# 09_-_COMMUNICATION.net
KiCad netlist of a schematic drawn in Altium Designer
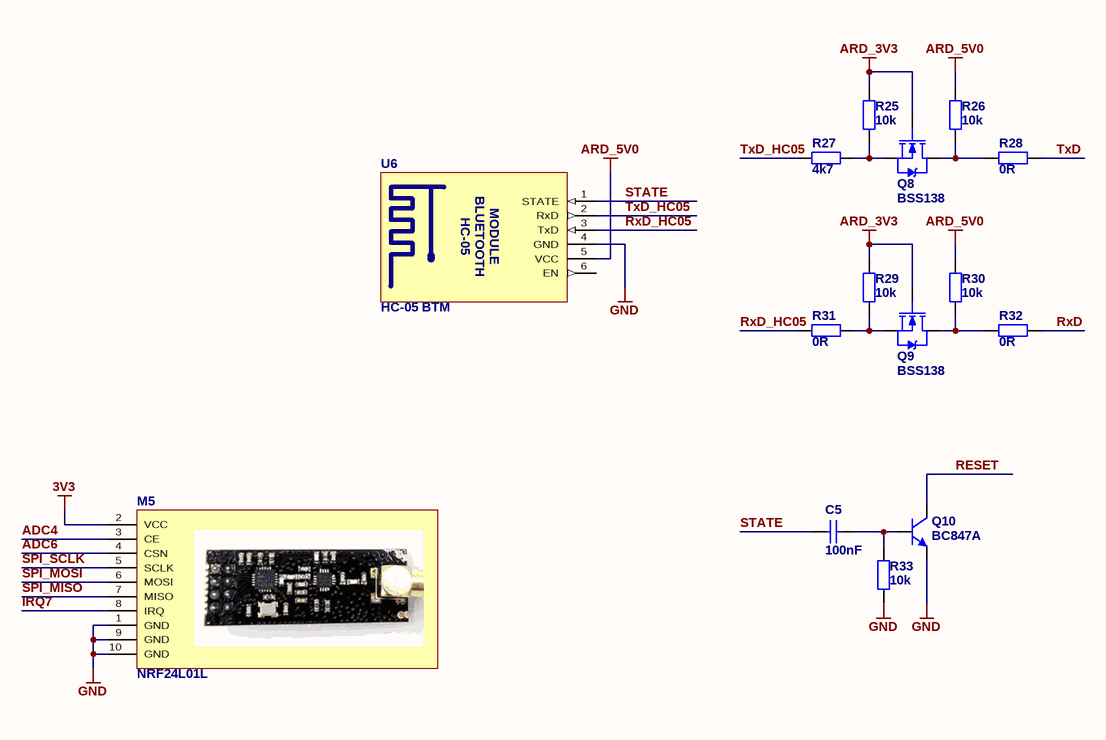
[diagram p0: [09] - COMMUNICATION.SchDoc]

(export (version "E")
  (design (tool "Eeschema 10.0.6"))
  (components
    (comp (ref "C5")
      (value "100nF")
      (footprint "C0805")
      (description "Capacitor")
      (libsource (lib "capacitors") (part "Cap"))
    )
    (comp (ref "M5")
      (value "NRF24L01L")
      (footprint "NRF24L01L")
      (description "Long Range Wireless Module R2 (1.1KM, PA+SMA)")
      (libsource (lib "wireless_modules") (part "NRF24L01L"))
    )
    (comp (ref "Q8")
      (value "BSS138")
      (footprint "SOT-23")
      (description "N-Channel Enhancement Mode Vertical DMOS FET")
      (fields (field (name "PUBLISHER") "Altium Limited"))
      (libsource (lib "transistors_mos") (part "BSS138"))
    )
    (comp (ref "Q9")
      (value "BSS138")
      (footprint "SOT-23")
      (description "N-Channel Enhancement Mode Vertical DMOS FET")
      (fields (field (name "PUBLISHER") "Altium Limited"))
      (libsource (lib "transistors_mos") (part "BSS138"))
    )
    (comp (ref "Q10")
      (value "BC847A")
      (footprint "SOT-23")
      (description "NPN General Purpose Transistor (VCE=45V, IC=100mA, HFE=110-220)")
      (libsource (lib "transistors_bjt") (part "BC847A"))
    )
    (comp (ref "R25")
      (value "10k")
      (footprint "R0805")
      (description "Resistor")
      (libsource (lib "resistors") (part "Res"))
    )
    (comp (ref "R26")
      (value "10k")
      (footprint "R0805")
      (description "Resistor")
      (libsource (lib "resistors") (part "Res"))
    )
    (comp (ref "R27")
      (value "4k7")
      (footprint "R0805")
      (description "Resistor")
      (libsource (lib "") (part "Res_1"))
    )
    (comp (ref "R28")
      (value "0R")
      (footprint "R0805")
      (description "Resistor")
      (libsource (lib "") (part "Res_1"))
    )
    (comp (ref "R29")
      (value "10k")
      (footprint "R0805")
      (description "Resistor")
      (libsource (lib "resistors") (part "Res"))
    )
    (comp (ref "R30")
      (value "10k")
      (footprint "R0805")
      (description "Resistor")
      (libsource (lib "resistors") (part "Res"))
    )
    (comp (ref "R31")
      (value "0R")
      (footprint "R0805")
      (description "Resistor")
      (libsource (lib "") (part "Res_1"))
    )
    (comp (ref "R32")
      (value "0R")
      (footprint "R0805")
      (description "Resistor")
      (libsource (lib "") (part "Res_1"))
    )
    (comp (ref "R33")
      (value "10k")
      (footprint "R0805")
      (description "Resistor")
      (libsource (lib "resistors") (part "Res"))
    )
    (comp (ref "U6")
      (value "HC-05 BTM")
      (footprint "HC-05_H")
      (description "HC-05 Bluetooth Module")
      (libsource (lib "wireless_modules") (part "HC-05_BTM"))
    )
  )
  (nets
    (net (code "1") (name "/ADC4") (class "Default")
      (node (ref "M5") (pin "3") (pinfunction "CE_3") (pintype "passive"))
    )
    (net (code "2") (name "/ADC6") (class "Default")
      (node (ref "M5") (pin "4") (pinfunction "CSN_4") (pintype "passive"))
    )
    (net (code "3") (name "/IRQ7") (class "Default")
      (node (ref "M5") (pin "8") (pinfunction "IRQ_8") (pintype "passive"))
    )
    (net (code "4") (name "/RESET") (class "Default")
      (node (ref "Q10") (pin "3") (pinfunction "C_3") (pintype "passive"))
    )
    (net (code "5") (name "/RxD") (class "Default")
      (node (ref "R32") (pin "2") (pinfunction "2_2") (pintype "passive"))
    )
    (net (code "6") (name "/RxD_HC05") (class "Default")
      (node (ref "R31") (pin "1") (pinfunction "1_1") (pintype "passive"))
      (node (ref "U6") (pin "3") (pinfunction "TxD_3") (pintype "input"))
    )
    (net (code "7") (name "/SPI_MISO") (class "Default")
      (node (ref "M5") (pin "7") (pinfunction "MISO_7") (pintype "passive"))
    )
    (net (code "8") (name "/SPI_MOSI") (class "Default")
      (node (ref "M5") (pin "6") (pinfunction "MOSI_6") (pintype "passive"))
    )
    (net (code "9") (name "/SPI_SCLK") (class "Default")
      (node (ref "M5") (pin "5") (pinfunction "SCLK_5") (pintype "passive"))
    )
    (net (code "10") (name "/STATE") (class "Default")
      (node (ref "C5") (pin "1") (pinfunction "1_1") (pintype "passive"))
      (node (ref "U6") (pin "1") (pinfunction "STATE_1") (pintype "input"))
    )
    (net (code "11") (name "/TxD") (class "Default")
      (node (ref "R28") (pin "2") (pinfunction "2_2") (pintype "passive"))
    )
    (net (code "12") (name "/TxD_HC05") (class "Default")
      (node (ref "R27") (pin "1") (pinfunction "1_1") (pintype "passive"))
      (node (ref "U6") (pin "2") (pinfunction "RxD_2") (pintype "output"))
    )
    (net (code "13") (name "3V3") (class "Default")
      (node (ref "M5") (pin "2") (pinfunction "VCC_2") (pintype "passive"))
    )
    (net (code "14") (name "ARD_3V3") (class "Default")
      (node (ref "Q8") (pin "1") (pinfunction "G_1") (pintype "passive"))
      (node (ref "Q9") (pin "1") (pinfunction "G_1") (pintype "passive"))
      (node (ref "R25") (pin "1") (pinfunction "1_1") (pintype "passive"))
      (node (ref "R29") (pin "1") (pinfunction "1_1") (pintype "passive"))
    )
    (net (code "15") (name "ARD_5V0") (class "Default")
      (node (ref "R26") (pin "1") (pinfunction "1_1") (pintype "passive"))
      (node (ref "R30") (pin "1") (pinfunction "1_1") (pintype "passive"))
      (node (ref "U6") (pin "5") (pinfunction "VCC_5") (pintype "power_in"))
    )
    (net (code "16") (name "GND") (class "Default")
      (node (ref "M5") (pin "1") (pinfunction "GND_1") (pintype "passive"))
      (node (ref "M5") (pin "10") (pinfunction "GND_10") (pintype "passive"))
      (node (ref "M5") (pin "9") (pinfunction "GND_9") (pintype "passive"))
      (node (ref "Q10") (pin "2") (pinfunction "E_2") (pintype "passive"))
      (node (ref "R33") (pin "2") (pinfunction "2_2") (pintype "passive"))
      (node (ref "U6") (pin "4") (pinfunction "GND_4") (pintype "power_in"))
    )
    (net (code "17") (name "Net-(Q8-D)") (class "Default")
      (node (ref "Q8") (pin "3") (pinfunction "D_3") (pintype "passive"))
      (node (ref "R26") (pin "2") (pinfunction "2_2") (pintype "passive"))
      (node (ref "R28") (pin "1") (pinfunction "1_1") (pintype "passive"))
    )
    (net (code "18") (name "Net-(Q8-S)") (class "Default")
      (node (ref "Q8") (pin "2") (pinfunction "S_2") (pintype "passive"))
      (node (ref "R25") (pin "2") (pinfunction "2_2") (pintype "passive"))
      (node (ref "R27") (pin "2") (pinfunction "2_2") (pintype "passive"))
    )
    (net (code "19") (name "Net-(Q9-D)") (class "Default")
      (node (ref "Q9") (pin "3") (pinfunction "D_3") (pintype "passive"))
      (node (ref "R30") (pin "2") (pinfunction "2_2") (pintype "passive"))
      (node (ref "R32") (pin "1") (pinfunction "1_1") (pintype "passive"))
    )
    (net (code "20") (name "Net-(Q9-S)") (class "Default")
      (node (ref "Q9") (pin "2") (pinfunction "S_2") (pintype "passive"))
      (node (ref "R29") (pin "2") (pinfunction "2_2") (pintype "passive"))
      (node (ref "R31") (pin "2") (pinfunction "2_2") (pintype "passive"))
    )
    (net (code "21") (name "Net-(Q10-B)") (class "Default")
      (node (ref "C5") (pin "2") (pinfunction "2_2") (pintype "passive"))
      (node (ref "Q10") (pin "1") (pinfunction "B_1") (pintype "passive"))
      (node (ref "R33") (pin "1") (pinfunction "1_1") (pintype "passive"))
    )
    (net (code "22") (name "unconnected-(U6-EN-Pad6)") (class "Default")
      (node (ref "U6") (pin "6") (pinfunction "EN_6") (pintype "output"))
    )
  )
)
